# OSD19001_BREAKOUTS.net
KiCad netlist of a schematic drawn in Altium Designer
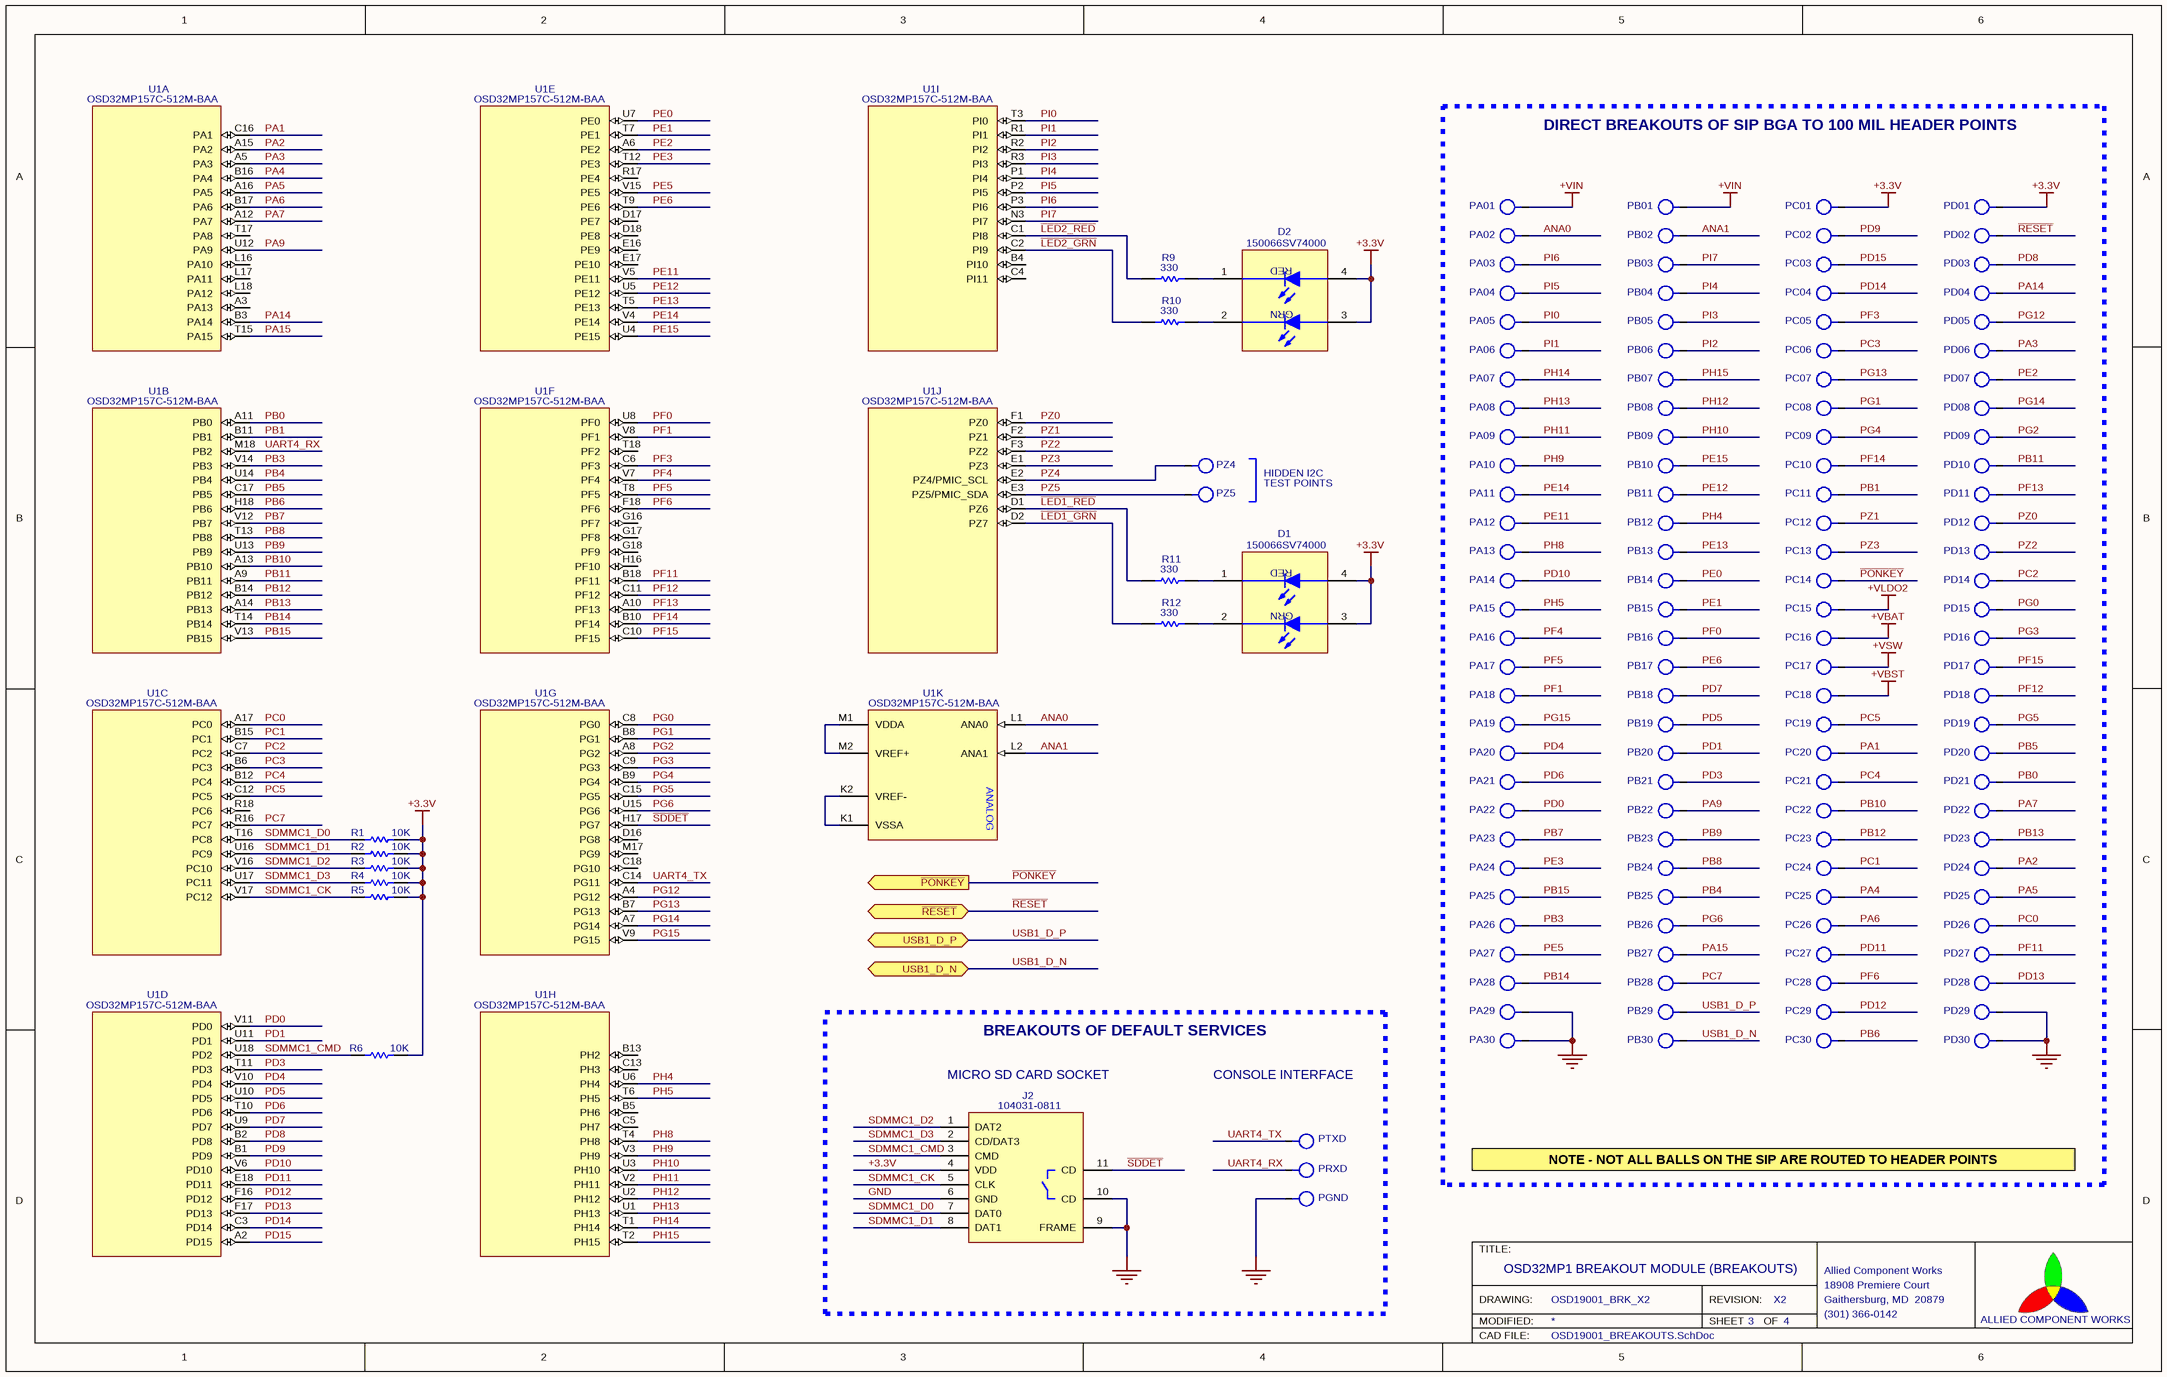
[diagram p0: OSD19001_BREAKOUTS.SchDoc]

(export (version "E")
  (design (tool "Eeschema 10.0.6"))
  (components
    (comp (ref "D1")
      (value "150066SV74000")
      (footprint "WURTH_DUAL_0606")
      (description "LED, Dual, 4-Wire, SMT")
      (libsource (lib "ACWSemiconductors") (part "LED_DUAL_0606_WURTH"))
    )
    (comp (ref "D2")
      (value "150066SV74000")
      (footprint "WURTH_DUAL_0606")
      (description "LED, Dual, 4-Wire, SMT")
      (libsource (lib "ACWSemiconductors") (part "LED_DUAL_0606_WURTH"))
    )
    (comp (ref "J2")
      (value "104031-0811")
      (footprint "MOLEX_104031-0811")
      (description "Micro SD Connector, With CD Switch")
      (libsource (lib "ACWConnectors") (part "SD_CARD_SW"))
    )
    (comp (ref "PA01")
      (value "TP")
      (footprint "LP_TESTPOINT_TH")
      (libsource (lib "ACWPrimitives") (part "TEST_POINT"))
    )
    (comp (ref "PA02")
      (value "TP")
      (footprint "LP_TESTPOINT_TH")
      (libsource (lib "ACWPrimitives") (part "TEST_POINT"))
    )
    (comp (ref "PA03")
      (value "TP")
      (footprint "LP_TESTPOINT_TH")
      (libsource (lib "ACWPrimitives") (part "TEST_POINT"))
    )
    (comp (ref "PA04")
      (value "TP")
      (footprint "LP_TESTPOINT_TH")
      (libsource (lib "ACWPrimitives") (part "TEST_POINT"))
    )
    (comp (ref "PA05")
      (value "TP")
      (footprint "LP_TESTPOINT_TH")
      (libsource (lib "ACWPrimitives") (part "TEST_POINT"))
    )
    (comp (ref "PA06")
      (value "TP")
      (footprint "LP_TESTPOINT_TH")
      (libsource (lib "ACWPrimitives") (part "TEST_POINT"))
    )
    (comp (ref "PA07")
      (value "TP")
      (footprint "LP_TESTPOINT_TH")
      (libsource (lib "ACWPrimitives") (part "TEST_POINT"))
    )
    (comp (ref "PA08")
      (value "TP")
      (footprint "LP_TESTPOINT_TH")
      (libsource (lib "ACWPrimitives") (part "TEST_POINT"))
    )
    (comp (ref "PA09")
      (value "TP")
      (footprint "LP_TESTPOINT_TH")
      (libsource (lib "ACWPrimitives") (part "TEST_POINT"))
    )
    (comp (ref "PA10")
      (value "TP")
      (footprint "LP_TESTPOINT_TH")
      (libsource (lib "ACWPrimitives") (part "TEST_POINT"))
    )
    (comp (ref "PA11")
      (value "TP")
      (footprint "LP_TESTPOINT_TH")
      (libsource (lib "ACWPrimitives") (part "TEST_POINT"))
    )
    (comp (ref "PA12")
      (value "TP")
      (footprint "LP_TESTPOINT_TH")
      (libsource (lib "ACWPrimitives") (part "TEST_POINT"))
    )
    (comp (ref "PA13")
      (value "TP")
      (footprint "LP_TESTPOINT_TH")
      (libsource (lib "ACWPrimitives") (part "TEST_POINT"))
    )
    (comp (ref "PA14")
      (value "TP")
      (footprint "LP_TESTPOINT_TH")
      (libsource (lib "ACWPrimitives") (part "TEST_POINT"))
    )
    (comp (ref "PA15")
      (value "TP")
      (footprint "LP_TESTPOINT_TH")
      (libsource (lib "ACWPrimitives") (part "TEST_POINT"))
    )
    (comp (ref "PA16")
      (value "TP")
      (footprint "LP_TESTPOINT_TH")
      (libsource (lib "ACWPrimitives") (part "TEST_POINT"))
    )
    (comp (ref "PA17")
      (value "TP")
      (footprint "LP_TESTPOINT_TH")
      (libsource (lib "ACWPrimitives") (part "TEST_POINT"))
    )
    (comp (ref "PA18")
      (value "TP")
      (footprint "LP_TESTPOINT_TH")
      (libsource (lib "ACWPrimitives") (part "TEST_POINT"))
    )
    (comp (ref "PA19")
      (value "TP")
      (footprint "LP_TESTPOINT_TH")
      (libsource (lib "ACWPrimitives") (part "TEST_POINT"))
    )
    (comp (ref "PA20")
      (value "TP")
      (footprint "LP_TESTPOINT_TH")
      (libsource (lib "ACWPrimitives") (part "TEST_POINT"))
    )
    (comp (ref "PA21")
      (value "TP")
      (footprint "LP_TESTPOINT_TH")
      (libsource (lib "ACWPrimitives") (part "TEST_POINT"))
    )
    (comp (ref "PA22")
      (value "TP")
      (footprint "LP_TESTPOINT_TH")
      (libsource (lib "ACWPrimitives") (part "TEST_POINT"))
    )
    (comp (ref "PA23")
      (value "TP")
      (footprint "LP_TESTPOINT_TH")
      (libsource (lib "ACWPrimitives") (part "TEST_POINT"))
    )
    (comp (ref "PA24")
      (value "TP")
      (footprint "LP_TESTPOINT_TH")
      (libsource (lib "ACWPrimitives") (part "TEST_POINT"))
    )
    (comp (ref "PA25")
      (value "TP")
      (footprint "LP_TESTPOINT_TH")
      (libsource (lib "ACWPrimitives") (part "TEST_POINT"))
    )
    (comp (ref "PA26")
      (value "TP")
      (footprint "LP_TESTPOINT_TH")
      (libsource (lib "ACWPrimitives") (part "TEST_POINT"))
    )
    (comp (ref "PA27")
      (value "TP")
      (footprint "LP_TESTPOINT_TH")
      (libsource (lib "ACWPrimitives") (part "TEST_POINT"))
    )
    (comp (ref "PA28")
      (value "TP")
      (footprint "LP_TESTPOINT_TH")
      (libsource (lib "ACWPrimitives") (part "TEST_POINT"))
    )
    (comp (ref "PA29")
      (value "TP")
      (footprint "LP_TESTPOINT_TH")
      (libsource (lib "ACWPrimitives") (part "TEST_POINT"))
    )
    (comp (ref "PA30")
      (value "TP")
      (footprint "LP_TESTPOINT_TH")
      (libsource (lib "ACWPrimitives") (part "TEST_POINT"))
    )
    (comp (ref "PB01")
      (value "TP")
      (footprint "LP_TESTPOINT_TH")
      (libsource (lib "ACWPrimitives") (part "TEST_POINT"))
    )
    (comp (ref "PB02")
      (value "TP")
      (footprint "LP_TESTPOINT_TH")
      (libsource (lib "ACWPrimitives") (part "TEST_POINT"))
    )
    (comp (ref "PB03")
      (value "TP")
      (footprint "LP_TESTPOINT_TH")
      (libsource (lib "ACWPrimitives") (part "TEST_POINT"))
    )
    (comp (ref "PB04")
      (value "TP")
      (footprint "LP_TESTPOINT_TH")
      (libsource (lib "ACWPrimitives") (part "TEST_POINT"))
    )
    (comp (ref "PB05")
      (value "TP")
      (footprint "LP_TESTPOINT_TH")
      (libsource (lib "ACWPrimitives") (part "TEST_POINT"))
    )
    (comp (ref "PB06")
      (value "TP")
      (footprint "LP_TESTPOINT_TH")
      (libsource (lib "ACWPrimitives") (part "TEST_POINT"))
    )
    (comp (ref "PB07")
      (value "TP")
      (footprint "LP_TESTPOINT_TH")
      (libsource (lib "ACWPrimitives") (part "TEST_POINT"))
    )
    (comp (ref "PB08")
      (value "TP")
      (footprint "LP_TESTPOINT_TH")
      (libsource (lib "ACWPrimitives") (part "TEST_POINT"))
    )
    (comp (ref "PB09")
      (value "TP")
      (footprint "LP_TESTPOINT_TH")
      (libsource (lib "ACWPrimitives") (part "TEST_POINT"))
    )
    (comp (ref "PB10")
      (value "TP")
      (footprint "LP_TESTPOINT_TH")
      (libsource (lib "ACWPrimitives") (part "TEST_POINT"))
    )
    (comp (ref "PB11")
      (value "TP")
      (footprint "LP_TESTPOINT_TH")
      (libsource (lib "ACWPrimitives") (part "TEST_POINT"))
    )
    (comp (ref "PB12")
      (value "TP")
      (footprint "LP_TESTPOINT_TH")
      (libsource (lib "ACWPrimitives") (part "TEST_POINT"))
    )
    (comp (ref "PB13")
      (value "TP")
      (footprint "LP_TESTPOINT_TH")
      (libsource (lib "ACWPrimitives") (part "TEST_POINT"))
    )
    (comp (ref "PB14")
      (value "TP")
      (footprint "LP_TESTPOINT_TH")
      (libsource (lib "ACWPrimitives") (part "TEST_POINT"))
    )
    (comp (ref "PB15")
      (value "TP")
      (footprint "LP_TESTPOINT_TH")
      (libsource (lib "ACWPrimitives") (part "TEST_POINT"))
    )
    (comp (ref "PB16")
      (value "TP")
      (footprint "LP_TESTPOINT_TH")
      (libsource (lib "ACWPrimitives") (part "TEST_POINT"))
    )
    (comp (ref "PB17")
      (value "TP")
      (footprint "LP_TESTPOINT_TH")
      (libsource (lib "ACWPrimitives") (part "TEST_POINT"))
    )
    (comp (ref "PB18")
      (value "TP")
      (footprint "LP_TESTPOINT_TH")
      (libsource (lib "ACWPrimitives") (part "TEST_POINT"))
    )
    (comp (ref "PB19")
      (value "TP")
      (footprint "LP_TESTPOINT_TH")
      (libsource (lib "ACWPrimitives") (part "TEST_POINT"))
    )
    (comp (ref "PB20")
      (value "TP")
      (footprint "LP_TESTPOINT_TH")
      (libsource (lib "ACWPrimitives") (part "TEST_POINT"))
    )
    (comp (ref "PB21")
      (value "TP")
      (footprint "LP_TESTPOINT_TH")
      (libsource (lib "ACWPrimitives") (part "TEST_POINT"))
    )
    (comp (ref "PB22")
      (value "TP")
      (footprint "LP_TESTPOINT_TH")
      (libsource (lib "ACWPrimitives") (part "TEST_POINT"))
    )
    (comp (ref "PB23")
      (value "TP")
      (footprint "LP_TESTPOINT_TH")
      (libsource (lib "ACWPrimitives") (part "TEST_POINT"))
    )
    (comp (ref "PB24")
      (value "TP")
      (footprint "LP_TESTPOINT_TH")
      (libsource (lib "ACWPrimitives") (part "TEST_POINT"))
    )
    (comp (ref "PB25")
      (value "TP")
      (footprint "LP_TESTPOINT_TH")
      (libsource (lib "ACWPrimitives") (part "TEST_POINT"))
    )
    (comp (ref "PB26")
      (value "TP")
      (footprint "LP_TESTPOINT_TH")
      (libsource (lib "ACWPrimitives") (part "TEST_POINT"))
    )
    (comp (ref "PB27")
      (value "TP")
      (footprint "LP_TESTPOINT_TH")
      (libsource (lib "ACWPrimitives") (part "TEST_POINT"))
    )
    (comp (ref "PB28")
      (value "TP")
      (footprint "LP_TESTPOINT_TH")
      (libsource (lib "ACWPrimitives") (part "TEST_POINT"))
    )
    (comp (ref "PB29")
      (value "TP")
      (footprint "LP_TESTPOINT_TH")
      (libsource (lib "ACWPrimitives") (part "TEST_POINT"))
    )
    (comp (ref "PB30")
      (value "TP")
      (footprint "LP_TESTPOINT_TH")
      (libsource (lib "ACWPrimitives") (part "TEST_POINT"))
    )
    (comp (ref "PC01")
      (value "TP")
      (footprint "LP_TESTPOINT_TH")
      (libsource (lib "ACWPrimitives") (part "TEST_POINT"))
    )
    (comp (ref "PC02")
      (value "TP")
      (footprint "LP_TESTPOINT_TH")
      (libsource (lib "ACWPrimitives") (part "TEST_POINT"))
    )
    (comp (ref "PC03")
      (value "TP")
      (footprint "LP_TESTPOINT_TH")
      (libsource (lib "ACWPrimitives") (part "TEST_POINT"))
    )
    (comp (ref "PC04")
      (value "TP")
      (footprint "LP_TESTPOINT_TH")
      (libsource (lib "ACWPrimitives") (part "TEST_POINT"))
    )
    (comp (ref "PC05")
      (value "TP")
      (footprint "LP_TESTPOINT_TH")
      (libsource (lib "ACWPrimitives") (part "TEST_POINT"))
    )
    (comp (ref "PC06")
      (value "TP")
      (footprint "LP_TESTPOINT_TH")
      (libsource (lib "ACWPrimitives") (part "TEST_POINT"))
    )
    (comp (ref "PC07")
      (value "TP")
      (footprint "LP_TESTPOINT_TH")
      (libsource (lib "ACWPrimitives") (part "TEST_POINT"))
    )
    (comp (ref "PC08")
      (value "TP")
      (footprint "LP_TESTPOINT_TH")
      (libsource (lib "ACWPrimitives") (part "TEST_POINT"))
    )
    (comp (ref "PC09")
      (value "TP")
      (footprint "LP_TESTPOINT_TH")
      (libsource (lib "ACWPrimitives") (part "TEST_POINT"))
    )
    (comp (ref "PC10")
      (value "TP")
      (footprint "LP_TESTPOINT_TH")
      (libsource (lib "ACWPrimitives") (part "TEST_POINT"))
    )
    (comp (ref "PC11")
      (value "TP")
      (footprint "LP_TESTPOINT_TH")
      (libsource (lib "ACWPrimitives") (part "TEST_POINT"))
    )
    (comp (ref "PC12")
      (value "TP")
      (footprint "LP_TESTPOINT_TH")
      (libsource (lib "ACWPrimitives") (part "TEST_POINT"))
    )
    (comp (ref "PC13")
      (value "TP")
      (footprint "LP_TESTPOINT_TH")
      (libsource (lib "ACWPrimitives") (part "TEST_POINT"))
    )
    (comp (ref "PC14")
      (value "TP")
      (footprint "LP_TESTPOINT_TH")
      (libsource (lib "ACWPrimitives") (part "TEST_POINT"))
    )
    (comp (ref "PC15")
      (value "TP")
      (footprint "LP_TESTPOINT_TH")
      (libsource (lib "ACWPrimitives") (part "TEST_POINT"))
    )
    (comp (ref "PC16")
      (value "TP")
      (footprint "LP_TESTPOINT_TH")
      (libsource (lib "ACWPrimitives") (part "TEST_POINT"))
    )
    (comp (ref "PC17")
      (value "TP")
      (footprint "LP_TESTPOINT_TH")
      (libsource (lib "ACWPrimitives") (part "TEST_POINT"))
    )
    (comp (ref "PC18")
      (value "TP")
      (footprint "LP_TESTPOINT_TH")
      (libsource (lib "ACWPrimitives") (part "TEST_POINT"))
    )
    (comp (ref "PC19")
      (value "TP")
      (footprint "LP_TESTPOINT_TH")
      (libsource (lib "ACWPrimitives") (part "TEST_POINT"))
    )
    (comp (ref "PC20")
      (value "TP")
      (footprint "LP_TESTPOINT_TH")
      (libsource (lib "ACWPrimitives") (part "TEST_POINT"))
    )
    (comp (ref "PC21")
      (value "TP")
      (footprint "LP_TESTPOINT_TH")
      (libsource (lib "ACWPrimitives") (part "TEST_POINT"))
    )
    (comp (ref "PC22")
      (value "TP")
      (footprint "LP_TESTPOINT_TH")
      (libsource (lib "ACWPrimitives") (part "TEST_POINT"))
    )
    (comp (ref "PC23")
      (value "TP")
      (footprint "LP_TESTPOINT_TH")
      (libsource (lib "ACWPrimitives") (part "TEST_POINT"))
    )
    (comp (ref "PC24")
      (value "TP")
      (footprint "LP_TESTPOINT_TH")
      (libsource (lib "ACWPrimitives") (part "TEST_POINT"))
    )
    (comp (ref "PC25")
      (value "TP")
      (footprint "LP_TESTPOINT_TH")
      (libsource (lib "ACWPrimitives") (part "TEST_POINT"))
    )
    (comp (ref "PC26")
      (value "TP")
      (footprint "LP_TESTPOINT_TH")
      (libsource (lib "ACWPrimitives") (part "TEST_POINT"))
    )
    (comp (ref "PC27")
      (value "TP")
      (footprint "LP_TESTPOINT_TH")
      (libsource (lib "ACWPrimitives") (part "TEST_POINT"))
    )
    (comp (ref "PC28")
      (value "TP")
      (footprint "LP_TESTPOINT_TH")
      (libsource (lib "ACWPrimitives") (part "TEST_POINT"))
    )
    (comp (ref "PC29")
      (value "TP")
      (footprint "LP_TESTPOINT_TH")
      (libsource (lib "ACWPrimitives") (part "TEST_POINT"))
    )
    (comp (ref "PC30")
      (value "TP")
      (footprint "LP_TESTPOINT_TH")
      (libsource (lib "ACWPrimitives") (part "TEST_POINT"))
    )
    (comp (ref "PD01")
      (value "TP")
      (footprint "LP_TESTPOINT_TH")
      (libsource (lib "ACWPrimitives") (part "TEST_POINT"))
    )
    (comp (ref "PD02")
      (value "TP")
      (footprint "LP_TESTPOINT_TH")
      (libsource (lib "ACWPrimitives") (part "TEST_POINT"))
    )
    (comp (ref "PD03")
      (value "TP")
      (footprint "LP_TESTPOINT_TH")
      (libsource (lib "ACWPrimitives") (part "TEST_POINT"))
    )
    (comp (ref "PD04")
      (value "TP")
      (footprint "LP_TESTPOINT_TH")
      (libsource (lib "ACWPrimitives") (part "TEST_POINT"))
    )
    (comp (ref "PD05")
      (value "TP")
      (footprint "LP_TESTPOINT_TH")
      (libsource (lib "ACWPrimitives") (part "TEST_POINT"))
    )
    (comp (ref "PD06")
      (value "TP")
      (footprint "LP_TESTPOINT_TH")
      (libsource (lib "ACWPrimitives") (part "TEST_POINT"))
    )
    (comp (ref "PD07")
      (value "TP")
      (footprint "LP_TESTPOINT_TH")
      (libsource (lib "ACWPrimitives") (part "TEST_POINT"))
    )
    (comp (ref "PD08")
      (value "TP")
      (footprint "LP_TESTPOINT_TH")
      (libsource (lib "ACWPrimitives") (part "TEST_POINT"))
    )
    (comp (ref "PD09")
      (value "TP")
      (footprint "LP_TESTPOINT_TH")
      (libsource (lib "ACWPrimitives") (part "TEST_POINT"))
    )
    (comp (ref "PD10")
      (value "TP")
      (footprint "LP_TESTPOINT_TH")
      (libsource (lib "ACWPrimitives") (part "TEST_POINT"))
    )
    (comp (ref "PD11")
      (value "TP")
      (footprint "LP_TESTPOINT_TH")
      (libsource (lib "ACWPrimitives") (part "TEST_POINT"))
    )
    (comp (ref "PD12")
      (value "TP")
      (footprint "LP_TESTPOINT_TH")
      (libsource (lib "ACWPrimitives") (part "TEST_POINT"))
    )
    (comp (ref "PD13")
      (value "TP")
      (footprint "LP_TESTPOINT_TH")
      (libsource (lib "ACWPrimitives") (part "TEST_POINT"))
    )
    (comp (ref "PD14")
      (value "TP")
      (footprint "LP_TESTPOINT_TH")
      (libsource (lib "ACWPrimitives") (part "TEST_POINT"))
    )
    (comp (ref "PD15")
      (value "TP")
      (footprint "LP_TESTPOINT_TH")
      (libsource (lib "ACWPrimitives") (part "TEST_POINT"))
    )
    (comp (ref "PD16")
      (value "TP")
      (footprint "LP_TESTPOINT_TH")
      (libsource (lib "ACWPrimitives") (part "TEST_POINT"))
    )
    (comp (ref "PD17")
      (value "TP")
      (footprint "LP_TESTPOINT_TH")
      (libsource (lib "ACWPrimitives") (part "TEST_POINT"))
    )
    (comp (ref "PD18")
      (value "TP")
      (footprint "LP_TESTPOINT_TH")
      (libsource (lib "ACWPrimitives") (part "TEST_POINT"))
    )
    (comp (ref "PD19")
      (value "TP")
      (footprint "LP_TESTPOINT_TH")
      (libsource (lib "ACWPrimitives") (part "TEST_POINT"))
    )
    (comp (ref "PD20")
      (value "TP")
      (footprint "LP_TESTPOINT_TH")
      (libsource (lib "ACWPrimitives") (part "TEST_POINT"))
    )
    (comp (ref "PD21")
      (value "TP")
      (footprint "LP_TESTPOINT_TH")
      (libsource (lib "ACWPrimitives") (part "TEST_POINT"))
    )
    (comp (ref "PD22")
      (value "TP")
      (footprint "LP_TESTPOINT_TH")
      (libsource (lib "ACWPrimitives") (part "TEST_POINT"))
    )
    (comp (ref "PD23")
      (value "TP")
      (footprint "LP_TESTPOINT_TH")
      (libsource (lib "ACWPrimitives") (part "TEST_POINT"))
    )
    (comp (ref "PD24")
      (value "TP")
      (footprint "LP_TESTPOINT_TH")
      (libsource (lib "ACWPrimitives") (part "TEST_POINT"))
    )
    (comp (ref "PD25")
      (value "TP")
      (footprint "LP_TESTPOINT_TH")
      (libsource (lib "ACWPrimitives") (part "TEST_POINT"))
    )
    (comp (ref "PD26")
      (value "TP")
      (footprint "LP_TESTPOINT_TH")
      (libsource (lib "ACWPrimitives") (part "TEST_POINT"))
    )
    (comp (ref "PD27")
      (value "TP")
      (footprint "LP_TESTPOINT_TH")
      (libsource (lib "ACWPrimitives") (part "TEST_POINT"))
    )
    (comp (ref "PD28")
      (value "TP")
      (footprint "LP_TESTPOINT_TH")
      (libsource (lib "ACWPrimitives") (part "TEST_POINT"))
    )
    (comp (ref "PD29")
      (value "TP")
      (footprint "LP_TESTPOINT_TH")
      (libsource (lib "ACWPrimitives") (part "TEST_POINT"))
    )
    (comp (ref "PD30")
      (value "TP")
      (footprint "LP_TESTPOINT_TH")
      (libsource (lib "ACWPrimitives") (part "TEST_POINT"))
    )
    (comp (ref "PGND")
      (value "TP")
      (footprint "LP_TESTPOINT_TH")
      (libsource (lib "ACWPrimitives") (part "TEST_POINT"))
    )
    (comp (ref "PRXD")
      (value "TP")
      (footprint "LP_TESTPOINT_TH")
      (libsource (lib "ACWPrimitives") (part "TEST_POINT"))
    )
    (comp (ref "PTXD")
      (value "TP")
      (footprint "LP_TESTPOINT_TH")
      (libsource (lib "ACWPrimitives") (part "TEST_POINT"))
    )
    (comp (ref "PZ4")
      (value "TP")
      (footprint "LP_TESTPOINT_SMT")
      (libsource (lib "ACWPrimitives") (part "TEST_POINT"))
    )
    (comp (ref "PZ5")
      (value "TP")
      (footprint "LP_TESTPOINT_SMT")
      (libsource (lib "ACWPrimitives") (part "TEST_POINT"))
    )
    (comp (ref "R1")
      (value "10K")
      (footprint "LP_0402_LOW")
      (fields (field (name "TOLERANCE") "5%") (field (name "POWER") "0.1W") (field (name "VOLTAGE") "50V"))
      (libsource (lib "ACWPrimitives") (part "RESISTOR"))
    )
    (comp (ref "R2")
      (value "10K")
      (footprint "LP_0402_LOW")
      (fields (field (name "TOLERANCE") "5%") (field (name "POWER") "0.1W") (field (name "VOLTAGE") "50V"))
      (libsource (lib "ACWPrimitives") (part "RESISTOR"))
    )
    (comp (ref "R3")
      (value "10K")
      (footprint "LP_0402_LOW")
      (fields (field (name "TOLERANCE") "5%") (field (name "POWER") "0.1W") (field (name "VOLTAGE") "50V"))
      (libsource (lib "ACWPrimitives") (part "RESISTOR"))
    )
    (comp (ref "R4")
      (value "10K")
      (footprint "LP_0402_LOW")
      (fields (field (name "TOLERANCE") "5%") (field (name "POWER") "0.1W") (field (name "VOLTAGE") "50V"))
      (libsource (lib "ACWPrimitives") (part "RESISTOR"))
    )
    (comp (ref "R5")
      (value "10K")
      (footprint "LP_0402_LOW")
      (fields (field (name "TOLERANCE") "5%") (field (name "POWER") "0.1W") (field (name "VOLTAGE") "50V"))
      (libsource (lib "ACWPrimitives") (part "RESISTOR"))
    )
    (comp (ref "R6")
      (value "10K")
      (footprint "LP_0402_LOW")
      (fields (field (name "TOLERANCE") "5%") (field (name "POWER") "0.1W") (field (name "VOLTAGE") "50V"))
      (libsource (lib "ACWPrimitives") (part "RESISTOR"))
    )
    (comp (ref "R9")
      (value "330")
      (footprint "LP_0402_LOW")
      (fields (field (name "TOLERANCE") "5%") (field (name "POWER") "0.1W") (field (name "VOLTAGE") "50V"))
      (libsource (lib "ACWPrimitives") (part "RESISTOR"))
    )
    (comp (ref "R10")
      (value "330")
      (footprint "LP_0402_LOW")
      (fields (field (name "TOLERANCE") "5%") (field (name "POWER") "0.1W") (field (name "VOLTAGE") "50V"))
      (libsource (lib "ACWPrimitives") (part "RESISTOR"))
    )
    (comp (ref "R11")
      (value "330")
      (footprint "LP_0402_LOW")
      (fields (field (name "TOLERANCE") "5%") (field (name "POWER") "0.1W") (field (name "VOLTAGE") "50V"))
      (libsource (lib "ACWPrimitives") (part "RESISTOR"))
    )
    (comp (ref "R12")
      (value "330")
      (footprint "LP_0402_LOW")
      (fields (field (name "TOLERANCE") "5%") (field (name "POWER") "0.1W") (field (name "VOLTAGE") "50V"))
      (libsource (lib "ACWPrimitives") (part "RESISTOR"))
    )
    (comp (ref "U1")
      (value "OSD32MP157C-512M-BAA")
      (footprint "BGA_OCTAVO_SIP_OSD32MP157C")
      (description "Octavo ST Processor SIP")
      (fields (field (name "MANUFACTURER") "Octavo Systems"))
      (libsource (lib "ACWModules") (part "OSD32MP157C"))
    )
  )
  (nets
    (net (code "1") (name "+3.3V") (class "Default")
      (node (ref "D1") (pin "3") (pinfunction "A_3") (pintype "passive"))
      (node (ref "D1") (pin "4") (pinfunction "A_4") (pintype "passive"))
      (node (ref "D2") (pin "3") (pinfunction "A_3") (pintype "passive"))
      (node (ref "D2") (pin "4") (pinfunction "A_4") (pintype "passive"))
      (node (ref "J2") (pin "4") (pinfunction "VDD_4") (pintype "passive"))
      (node (ref "PC01") (pin "1") (pinfunction "1_1") (pintype "passive"))
      (node (ref "PD01") (pin "1") (pinfunction "1_1") (pintype "passive"))
      (node (ref "R1") (pin "2") (pinfunction "2_2") (pintype "passive"))
      (node (ref "R2") (pin "2") (pinfunction "2_2") (pintype "passive"))
      (node (ref "R3") (pin "2") (pinfunction "2_2") (pintype "passive"))
      (node (ref "R4") (pin "2") (pinfunction "2_2") (pintype "passive"))
      (node (ref "R5") (pin "2") (pinfunction "2_2") (pintype "passive"))
      (node (ref "R6") (pin "2") (pinfunction "2_2") (pintype "passive"))
    )
    (net (code "2") (name "+VBAT") (class "Default")
      (node (ref "PC16") (pin "1") (pinfunction "1_1") (pintype "passive"))
    )
    (net (code "3") (name "+VBST") (class "Default")
      (node (ref "PC18") (pin "1") (pinfunction "1_1") (pintype "passive"))
    )
    (net (code "4") (name "+VIN") (class "Default")
      (node (ref "PA01") (pin "1") (pinfunction "1_1") (pintype "passive"))
      (node (ref "PB01") (pin "1") (pinfunction "1_1") (pintype "passive"))
    )
    (net (code "5") (name "+VLDO2") (class "Default")
      (node (ref "PC15") (pin "1") (pinfunction "1_1") (pintype "passive"))
    )
    (net (code "6") (name "+VSW") (class "Default")
      (node (ref "PC17") (pin "1") (pinfunction "1_1") (pintype "passive"))
    )
    (net (code "7") (name "/ANA0") (class "Default")
      (node (ref "PA02") (pin "1") (pinfunction "1_1") (pintype "passive"))
      (node (ref "U1") (pin "L1") (pinfunction "ANA0_L1") (pintype "input"))
    )
    (net (code "8") (name "/ANA1") (class "Default")
      (node (ref "PB02") (pin "1") (pinfunction "1_1") (pintype "passive"))
      (node (ref "U1") (pin "L2") (pinfunction "ANA1_L2") (pintype "input"))
    )
    (net (code "9") (name "/LED1_GRN") (class "Default")
      (node (ref "R12") (pin "1") (pinfunction "1_1") (pintype "passive"))
      (node (ref "U1") (pin "D2") (pinfunction "PZ7_D2") (pintype "bidirectional"))
    )
    (net (code "10") (name "/LED1_RED") (class "Default")
      (node (ref "R11") (pin "1") (pinfunction "1_1") (pintype "passive"))
      (node (ref "U1") (pin "D1") (pinfunction "PZ6_D1") (pintype "bidirectional"))
    )
    (net (code "11") (name "/LED2_GRN") (class "Default")
      (node (ref "R10") (pin "1") (pinfunction "1_1") (pintype "passive"))
      (node (ref "U1") (pin "C2") (pinfunction "PI9_C2") (pintype "bidirectional"))
    )
    (net (code "12") (name "/LED2_RED") (class "Default")
      (node (ref "R9") (pin "1") (pinfunction "1_1") (pintype "passive"))
      (node (ref "U1") (pin "C1") (pinfunction "PI8_C1") (pintype "bidirectional"))
    )
    (net (code "13") (name "/PA1") (class "Default")
      (node (ref "PC20") (pin "1") (pinfunction "1_1") (pintype "passive"))
      (node (ref "U1") (pin "C16") (pinfunction "PA1_C16") (pintype "bidirectional"))
    )
    (net (code "14") (name "/PA2") (class "Default")
      (node (ref "PD24") (pin "1") (pinfunction "1_1") (pintype "passive"))
      (node (ref "U1") (pin "A15") (pinfunction "PA2_A15") (pintype "bidirectional"))
    )
    (net (code "15") (name "/PA3") (class "Default")
      (node (ref "PD06") (pin "1") (pinfunction "1_1") (pintype "passive"))
      (node (ref "U1") (pin "A5") (pinfunction "PA3_A5") (pintype "bidirectional"))
    )
    (net (code "16") (name "/PA4") (class "Default")
      (node (ref "PC25") (pin "1") (pinfunction "1_1") (pintype "passive"))
      (node (ref "U1") (pin "B16") (pinfunction "PA4_B16") (pintype "bidirectional"))
    )
    (net (code "17") (name "/PA5") (class "Default")
      (node (ref "PD25") (pin "1") (pinfunction "1_1") (pintype "passive"))
      (node (ref "U1") (pin "A16") (pinfunction "PA5_A16") (pintype "bidirectional"))
    )
    (net (code "18") (name "/PA6") (class "Default")
      (node (ref "PC26") (pin "1") (pinfunction "1_1") (pintype "passive"))
      (node (ref "U1") (pin "B17") (pinfunction "PA6_B17") (pintype "bidirectional"))
    )
    (net (code "19") (name "/PA7") (class "Default")
      (node (ref "PD22") (pin "1") (pinfunction "1_1") (pintype "passive"))
      (node (ref "U1") (pin "A12") (pinfunction "PA7_A12") (pintype "bidirectional"))
    )
    (net (code "20") (name "/PA9") (class "Default")
      (node (ref "PB22") (pin "1") (pinfunction "1_1") (pintype "passive"))
      (node (ref "U1") (pin "U12") (pinfunction "PA9_U12") (pintype "bidirectional"))
    )
    (net (code "21") (name "/PA14") (class "Default")
      (node (ref "PD04") (pin "1") (pinfunction "1_1") (pintype "passive"))
      (node (ref "U1") (pin "B3") (pinfunction "PA14_B3") (pintype "bidirectional"))
    )
    (net (code "22") (name "/PA15") (class "Default")
      (node (ref "PB27") (pin "1") (pinfunction "1_1") (pintype "passive"))
      (node (ref "U1") (pin "T15") (pinfunction "PA15_T15") (pintype "bidirectional"))
    )
    (net (code "23") (name "/PB0") (class "Default")
      (node (ref "PD21") (pin "1") (pinfunction "1_1") (pintype "passive"))
      (node (ref "U1") (pin "A11") (pinfunction "PB0_A11") (pintype "bidirectional"))
    )
    (net (code "24") (name "/PB1") (class "Default")
      (node (ref "PC11") (pin "1") (pinfunction "1_1") (pintype "passive"))
      (node (ref "U1") (pin "B11") (pinfunction "PB1_B11") (pintype "bidirectional"))
    )
    (net (code "25") (name "/PB3") (class "Default")
      (node (ref "PA26") (pin "1") (pinfunction "1_1") (pintype "passive"))
      (node (ref "U1") (pin "V14") (pinfunction "PB3_V14") (pintype "bidirectional"))
    )
    (net (code "26") (name "/PB4") (class "Default")
      (node (ref "PB25") (pin "1") (pinfunction "1_1") (pintype "passive"))
      (node (ref "U1") (pin "U14") (pinfunction "PB4_U14") (pintype "bidirectional"))
    )
    (net (code "27") (name "/PB5") (class "Default")
      (node (ref "PD20") (pin "1") (pinfunction "1_1") (pintype "passive"))
      (node (ref "U1") (pin "C17") (pinfunction "PB5_C17") (pintype "bidirectional"))
    )
    (net (code "28") (name "/PB6") (class "Default")
      (node (ref "PC30") (pin "1") (pinfunction "1_1") (pintype "passive"))
      (node (ref "U1") (pin "H18") (pinfunction "PB6_H18") (pintype "bidirectional"))
    )
    (net (code "29") (name "/PB7") (class "Default")
      (node (ref "PA23") (pin "1") (pinfunction "1_1") (pintype "passive"))
      (node (ref "U1") (pin "V12") (pinfunction "PB7_V12") (pintype "bidirectional"))
    )
    (net (code "30") (name "/PB8") (class "Default")
      (node (ref "PB24") (pin "1") (pinfunction "1_1") (pintype "passive"))
      (node (ref "U1") (pin "T13") (pinfunction "PB8_T13") (pintype "bidirectional"))
    )
    (net (code "31") (name "/PB9") (class "Default")
      (node (ref "PB23") (pin "1") (pinfunction "1_1") (pintype "passive"))
      (node (ref "U1") (pin "U13") (pinfunction "PB9_U13") (pintype "bidirectional"))
    )
    (net (code "32") (name "/PB10") (class "Default")
      (node (ref "PC22") (pin "1") (pinfunction "1_1") (pintype "passive"))
      (node (ref "U1") (pin "A13") (pinfunction "PB10_A13") (pintype "bidirectional"))
    )
    (net (code "33") (name "/PB11") (class "Default")
      (node (ref "PD10") (pin "1") (pinfunction "1_1") (pintype "passive"))
      (node (ref "U1") (pin "A9") (pinfunction "PB11_A9") (pintype "bidirectional"))
    )
    (net (code "34") (name "/PB12") (class "Default")
      (node (ref "PC23") (pin "1") (pinfunction "1_1") (pintype "passive"))
      (node (ref "U1") (pin "B14") (pinfunction "PB12_B14") (pintype "bidirectional"))
    )
    (net (code "35") (name "/PB13") (class "Default")
      (node (ref "PD23") (pin "1") (pinfunction "1_1") (pintype "passive"))
      (node (ref "U1") (pin "A14") (pinfunction "PB13_A14") (pintype "bidirectional"))
    )
    (net (code "36") (name "/PB14") (class "Default")
      (node (ref "PA28") (pin "1") (pinfunction "1_1") (pintype "passive"))
      (node (ref "U1") (pin "T14") (pinfunction "PB14_T14") (pintype "bidirectional"))
    )
    (net (code "37") (name "/PB15") (class "Default")
      (node (ref "PA25") (pin "1") (pinfunction "1_1") (pintype "passive"))
      (node (ref "U1") (pin "V13") (pinfunction "PB15_V13") (pintype "bidirectional"))
    )
    (net (code "38") (name "/PC0") (class "Default")
      (node (ref "PD26") (pin "1") (pinfunction "1_1") (pintype "passive"))
      (node (ref "U1") (pin "A17") (pinfunction "PC0_A17") (pintype "bidirectional"))
    )
    (net (code "39") (name "/PC1") (class "Default")
      (node (ref "PC24") (pin "1") (pinfunction "1_1") (pintype "passive"))
      (node (ref "U1") (pin "B15") (pinfunction "PC1_B15") (pintype "bidirectional"))
    )
    (net (code "40") (name "/PC2") (class "Default")
      (node (ref "PD14") (pin "1") (pinfunction "1_1") (pintype "passive"))
      (node (ref "U1") (pin "C7") (pinfunction "PC2_C7") (pintype "bidirectional"))
    )
    (net (code "41") (name "/PC3") (class "Default")
      (node (ref "PC06") (pin "1") (pinfunction "1_1") (pintype "passive"))
      (node (ref "U1") (pin "B6") (pinfunction "PC3_B6") (pintype "bidirectional"))
    )
    (net (code "42") (name "/PC4") (class "Default")
      (node (ref "PC21") (pin "1") (pinfunction "1_1") (pintype "passive"))
      (node (ref "U1") (pin "B12") (pinfunction "PC4_B12") (pintype "bidirectional"))
    )
    (net (code "43") (name "/PC5") (class "Default")
      (node (ref "PC19") (pin "1") (pinfunction "1_1") (pintype "passive"))
      (node (ref "U1") (pin "C12") (pinfunction "PC5_C12") (pintype "bidirectional"))
    )
    (net (code "44") (name "/PC7") (class "Default")
      (node (ref "PB28") (pin "1") (pinfunction "1_1") (pintype "passive"))
      (node (ref "U1") (pin "R16") (pinfunction "PC7_R16") (pintype "bidirectional"))
    )
    (net (code "45") (name "/PD0") (class "Default")
      (node (ref "PA22") (pin "1") (pinfunction "1_1") (pintype "passive"))
      (node (ref "U1") (pin "V11") (pinfunction "PD0_V11") (pintype "bidirectional"))
    )
    (net (code "46") (name "/PD1") (class "Default")
      (node (ref "PB20") (pin "1") (pinfunction "1_1") (pintype "passive"))
      (node (ref "U1") (pin "U11") (pinfunction "PD1_U11") (pintype "bidirectional"))
    )
    (net (code "47") (name "/PD3") (class "Default")
      (node (ref "PB21") (pin "1") (pinfunction "1_1") (pintype "passive"))
      (node (ref "U1") (pin "T11") (pinfunction "PD3_T11") (pintype "bidirectional"))
    )
    (net (code "48") (name "/PD4") (class "Default")
      (node (ref "PA20") (pin "1") (pinfunction "1_1") (pintype "passive"))
      (node (ref "U1") (pin "V10") (pinfunction "PD4_V10") (pintype "bidirectional"))
    )
    (net (code "49") (name "/PD5") (class "Default")
      (node (ref "PB19") (pin "1") (pinfunction "1_1") (pintype "passive"))
      (node (ref "U1") (pin "U10") (pinfunction "PD5_U10") (pintype "bidirectional"))
    )
    (net (code "50") (name "/PD6") (class "Default")
      (node (ref "PA21") (pin "1") (pinfunction "1_1") (pintype "passive"))
      (node (ref "U1") (pin "T10") (pinfunction "PD6_T10") (pintype "bidirectional"))
    )
    (net (code "51") (name "/PD7") (class "Default")
      (node (ref "PB18") (pin "1") (pinfunction "1_1") (pintype "passive"))
      (node (ref "U1") (pin "U9") (pinfunction "PD7_U9") (pintype "bidirectional"))
    )
    (net (code "52") (name "/PD8") (class "Default")
      (node (ref "PD03") (pin "1") (pinfunction "1_1") (pintype "passive"))
      (node (ref "U1") (pin "B2") (pinfunction "PD8_B2") (pintype "bidirectional"))
    )
    (net (code "53") (name "/PD9") (class "Default")
      (node (ref "PC02") (pin "1") (pinfunction "1_1") (pintype "passive"))
      (node (ref "U1") (pin "B1") (pinfunction "PD9_B1") (pintype "bidirectional"))
    )
    (net (code "54") (name "/PD10") (class "Default")
      (node (ref "PA14") (pin "1") (pinfunction "1_1") (pintype "passive"))
      (node (ref "U1") (pin "V6") (pinfunction "PD10_V6") (pintype "bidirectional"))
    )
    (net (code "55") (name "/PD11") (class "Default")
      (node (ref "PC27") (pin "1") (pinfunction "1_1") (pintype "passive"))
      (node (ref "U1") (pin "E18") (pinfunction "PD11_E18") (pintype "bidirectional"))
    )
    (net (code "56") (name "/PD12") (class "Default")
      (node (ref "PC29") (pin "1") (pinfunction "1_1") (pintype "passive"))
      (node (ref "U1") (pin "F16") (pinfunction "PD12_F16") (pintype "bidirectional"))
    )
    (net (code "57") (name "/PD13") (class "Default")
      (node (ref "PD28") (pin "1") (pinfunction "1_1") (pintype "passive"))
      (node (ref "U1") (pin "F17") (pinfunction "PD13_F17") (pintype "bidirectional"))
    )
    (net (code "58") (name "/PD14") (class "Default")
      (node (ref "PC04") (pin "1") (pinfunction "1_1") (pintype "passive"))
      (node (ref "U1") (pin "C3") (pinfunction "PD14_C3") (pintype "bidirectional"))
    )
    (net (code "59") (name "/PD15") (class "Default")
      (node (ref "PC03") (pin "1") (pinfunction "1_1") (pintype "passive"))
      (node (ref "U1") (pin "A2") (pinfunction "PD15_A2") (pintype "bidirectional"))
    )
    (net (code "60") (name "/PE0") (class "Default")
      (node (ref "PB14") (pin "1") (pinfunction "1_1") (pintype "passive"))
      (node (ref "U1") (pin "U7") (pinfunction "PE0_U7") (pintype "bidirectional"))
    )
    (net (code "61") (name "/PE1") (class "Default")
      (node (ref "PB15") (pin "1") (pinfunction "1_1") (pintype "passive"))
      (node (ref "U1") (pin "T7") (pinfunction "PE1_T7") (pintype "bidirectional"))
    )
    (net (code "62") (name "/PE2") (class "Default")
      (node (ref "PD07") (pin "1") (pinfunction "1_1") (pintype "passive"))
      (node (ref "U1") (pin "A6") (pinfunction "PE2_A6") (pintype "bidirectional"))
    )
    (net (code "63") (name "/PE3") (class "Default")
      (node (ref "PA24") (pin "1") (pinfunction "1_1") (pintype "passive"))
      (node (ref "U1") (pin "T12") (pinfunction "PE3_T12") (pintype "bidirectional"))
    )
    (net (code "64") (name "/PE5") (class "Default")
      (node (ref "PA27") (pin "1") (pinfunction "1_1") (pintype "passive"))
      (node (ref "U1") (pin "V15") (pinfunction "PE5_V15") (pintype "bidirectional"))
    )
    (net (code "65") (name "/PE6") (class "Default")
      (node (ref "PB17") (pin "1") (pinfunction "1_1") (pintype "passive"))
      (node (ref "U1") (pin "T9") (pinfunction "PE6_T9") (pintype "bidirectional"))
    )
    (net (code "66") (name "/PE11") (class "Default")
      (node (ref "PA12") (pin "1") (pinfunction "1_1") (pintype "passive"))
      (node (ref "U1") (pin "V5") (pinfunction "PE11_V5") (pintype "bidirectional"))
    )
    (net (code "67") (name "/PE12") (class "Default")
      (node (ref "PB11") (pin "1") (pinfunction "1_1") (pintype "passive"))
      (node (ref "U1") (pin "U5") (pinfunction "PE12_U5") (pintype "bidirectional"))
    )
    (net (code "68") (name "/PE13") (class "Default")
      (node (ref "PB13") (pin "1") (pinfunction "1_1") (pintype "passive"))
      (node (ref "U1") (pin "T5") (pinfunction "PE13_T5") (pintype "bidirectional"))
    )
    (net (code "69") (name "/PE14") (class "Default")
      (node (ref "PA11") (pin "1") (pinfunction "1_1") (pintype "passive"))
      (node (ref "U1") (pin "V4") (pinfunction "PE14_V4") (pintype "bidirectional"))
    )
    (net (code "70") (name "/PE15") (class "Default")
      (node (ref "PB10") (pin "1") (pinfunction "1_1") (pintype "passive"))
      (node (ref "U1") (pin "U4") (pinfunction "PE15_U4") (pintype "bidirectional"))
    )
    (net (code "71") (name "/PF0") (class "Default")
      (node (ref "PB16") (pin "1") (pinfunction "1_1") (pintype "passive"))
      (node (ref "U1") (pin "U8") (pinfunction "PF0_U8") (pintype "bidirectional"))
    )
    (net (code "72") (name "/PF1") (class "Default")
      (node (ref "PA18") (pin "1") (pinfunction "1_1") (pintype "passive"))
      (node (ref "U1") (pin "V8") (pinfunction "PF1_V8") (pintype "bidirectional"))
    )
    (net (code "73") (name "/PF3") (class "Default")
      (node (ref "PC05") (pin "1") (pinfunction "1_1") (pintype "passive"))
      (node (ref "U1") (pin "C6") (pinfunction "PF3_C6") (pintype "bidirectional"))
    )
    (net (code "74") (name "/PF4") (class "Default")
      (node (ref "PA16") (pin "1") (pinfunction "1_1") (pintype "passive"))
      (node (ref "U1") (pin "V7") (pinfunction "PF4_V7") (pintype "bidirectional"))
    )
    (net (code "75") (name "/PF5") (class "Default")
      (node (ref "PA17") (pin "1") (pinfunction "1_1") (pintype "passive"))
      (node (ref "U1") (pin "T8") (pinfunction "PF5_T8") (pintype "bidirectional"))
    )
    (net (code "76") (name "/PF6") (class "Default")
      (node (ref "PC28") (pin "1") (pinfunction "1_1") (pintype "passive"))
      (node (ref "U1") (pin "F18") (pinfunction "PF6_F18") (pintype "bidirectional"))
    )
    (net (code "77") (name "/PF11") (class "Default")
      (node (ref "PD27") (pin "1") (pinfunction "1_1") (pintype "passive"))
      (node (ref "U1") (pin "B18") (pinfunction "PF11_B18") (pintype "bidirectional"))
    )
    (net (code "78") (name "/PF12") (class "Default")
      (node (ref "PD18") (pin "1") (pinfunction "1_1") (pintype "passive"))
      (node (ref "U1") (pin "C11") (pinfunction "PF12_C11") (pintype "bidirectional"))
    )
    (net (code "79") (name "/PF13") (class "Default")
      (node (ref "PD11") (pin "1") (pinfunction "1_1") (pintype "passive"))
      (node (ref "U1") (pin "A10") (pinfunction "PF13_A10") (pintype "bidirectional"))
    )
    (net (code "80") (name "/PF14") (class "Default")
      (node (ref "PC10") (pin "1") (pinfunction "1_1") (pintype "passive"))
      (node (ref "U1") (pin "B10") (pinfunction "PF14_B10") (pintype "bidirectional"))
    )
    (net (code "81") (name "/PF15") (class "Default")
      (node (ref "PD17") (pin "1") (pinfunction "1_1") (pintype "passive"))
      (node (ref "U1") (pin "C10") (pinfunction "PF15_C10") (pintype "bidirectional"))
    )
    (net (code "82") (name "/PG0") (class "Default")
      (node (ref "PD15") (pin "1") (pinfunction "1_1") (pintype "passive"))
      (node (ref "U1") (pin "C8") (pinfunction "PG0_C8") (pintype "bidirectional"))
    )
    (net (code "83") (name "/PG1") (class "Default")
      (node (ref "PC08") (pin "1") (pinfunction "1_1") (pintype "passive"))
      (node (ref "U1") (pin "B8") (pinfunction "PG1_B8") (pintype "bidirectional"))
    )
    (net (code "84") (name "/PG2") (class "Default")
      (node (ref "PD09") (pin "1") (pinfunction "1_1") (pintype "passive"))
      (node (ref "U1") (pin "A8") (pinfunction "PG2_A8") (pintype "bidirectional"))
    )
    (net (code "85") (name "/PG3") (class "Default")
      (node (ref "PD16") (pin "1") (pinfunction "1_1") (pintype "passive"))
      (node (ref "U1") (pin "C9") (pinfunction "PG3_C9") (pintype "bidirectional"))
    )
    (net (code "86") (name "/PG4") (class "Default")
      (node (ref "PC09") (pin "1") (pinfunction "1_1") (pintype "passive"))
      (node (ref "U1") (pin "B9") (pinfunction "PG4_B9") (pintype "bidirectional"))
    )
    (net (code "87") (name "/PG5") (class "Default")
      (node (ref "PD19") (pin "1") (pinfunction "1_1") (pintype "passive"))
      (node (ref "U1") (pin "C15") (pinfunction "PG5_C15") (pintype "bidirectional"))
    )
    (net (code "88") (name "/PG6") (class "Default")
      (node (ref "PB26") (pin "1") (pinfunction "1_1") (pintype "passive"))
      (node (ref "U1") (pin "U15") (pinfunction "PG6_U15") (pintype "bidirectional"))
    )
    (net (code "89") (name "/PG12") (class "Default")
      (node (ref "PD05") (pin "1") (pinfunction "1_1") (pintype "passive"))
      (node (ref "U1") (pin "A4") (pinfunction "PG12_A4") (pintype "bidirectional"))
    )
    (net (code "90") (name "/PG13") (class "Default")
      (node (ref "PC07") (pin "1") (pinfunction "1_1") (pintype "passive"))
      (node (ref "U1") (pin "B7") (pinfunction "PG13_B7") (pintype "bidirectional"))
    )
    (net (code "91") (name "/PG14") (class "Default")
      (node (ref "PD08") (pin "1") (pinfunction "1_1") (pintype "passive"))
      (node (ref "U1") (pin "A7") (pinfunction "PG14_A7") (pintype "bidirectional"))
    )
    (net (code "92") (name "/PG15") (class "Default")
      (node (ref "PA19") (pin "1") (pinfunction "1_1") (pintype "passive"))
      (node (ref "U1") (pin "V9") (pinfunction "PG15_V9") (pintype "bidirectional"))
    )
    (net (code "93") (name "/PH4") (class "Default")
      (node (ref "PB12") (pin "1") (pinfunction "1_1") (pintype "passive"))
      (node (ref "U1") (pin "U6") (pinfunction "PH4_U6") (pintype "bidirectional"))
    )
    (net (code "94") (name "/PH5") (class "Default")
      (node (ref "PA15") (pin "1") (pinfunction "1_1") (pintype "passive"))
      (node (ref "U1") (pin "T6") (pinfunction "PH5_T6") (pintype "bidirectional"))
    )
    (net (code "95") (name "/PH8") (class "Default")
      (node (ref "PA13") (pin "1") (pinfunction "1_1") (pintype "passive"))
      (node (ref "U1") (pin "T4") (pinfunction "PH8_T4") (pintype "bidirectional"))
    )
    (net (code "96") (name "/PH9") (class "Default")
      (node (ref "PA10") (pin "1") (pinfunction "1_1") (pintype "passive"))
      (node (ref "U1") (pin "V3") (pinfunction "PH9_V3") (pintype "bidirectional"))
    )
    (net (code "97") (name "/PH10") (class "Default")
      (node (ref "PB09") (pin "1") (pinfunction "1_1") (pintype "passive"))
      (node (ref "U1") (pin "U3") (pinfunction "PH10_U3") (pintype "bidirectional"))
    )
    (net (code "98") (name "/PH11") (class "Default")
      (node (ref "PA09") (pin "1") (pinfunction "1_1") (pintype "passive"))
      (node (ref "U1") (pin "V2") (pinfunction "PH11_V2") (pintype "bidirectional"))
    )
    (net (code "99") (name "/PH12") (class "Default")
      (node (ref "PB08") (pin "1") (pinfunction "1_1") (pintype "passive"))
      (node (ref "U1") (pin "U2") (pinfunction "PH12_U2") (pintype "bidirectional"))
    )
    (net (code "100") (name "/PH13") (class "Default")
      (node (ref "PA08") (pin "1") (pinfunction "1_1") (pintype "passive"))
      (node (ref "U1") (pin "U1") (pinfunction "PH13_U1") (pintype "bidirectional"))
    )
    (net (code "101") (name "/PH14") (class "Default")
      (node (ref "PA07") (pin "1") (pinfunction "1_1") (pintype "passive"))
      (node (ref "U1") (pin "T1") (pinfunction "PH14_T1") (pintype "bidirectional"))
    )
    (net (code "102") (name "/PH15") (class "Default")
      (node (ref "PB07") (pin "1") (pinfunction "1_1") (pintype "passive"))
      (node (ref "U1") (pin "T2") (pinfunction "PH15_T2") (pintype "bidirectional"))
    )
    (net (code "103") (name "/PI0") (class "Default")
      (node (ref "PA05") (pin "1") (pinfunction "1_1") (pintype "passive"))
      (node (ref "U1") (pin "T3") (pinfunction "PI0_T3") (pintype "bidirectional"))
    )
    (net (code "104") (name "/PI1") (class "Default")
      (node (ref "PA06") (pin "1") (pinfunction "1_1") (pintype "passive"))
      (node (ref "U1") (pin "R1") (pinfunction "PI1_R1") (pintype "bidirectional"))
    )
    (net (code "105") (name "/PI2") (class "Default")
      (node (ref "PB06") (pin "1") (pinfunction "1_1") (pintype "passive"))
      (node (ref "U1") (pin "R2") (pinfunction "PI2_R2") (pintype "bidirectional"))
    )
    (net (code "106") (name "/PI3") (class "Default")
      (node (ref "PB05") (pin "1") (pinfunction "1_1") (pintype "passive"))
      (node (ref "U1") (pin "R3") (pinfunction "PI3_R3") (pintype "bidirectional"))
    )
    (net (code "107") (name "/PI4") (class "Default")
      (node (ref "PB04") (pin "1") (pinfunction "1_1") (pintype "passive"))
      (node (ref "U1") (pin "P1") (pinfunction "PI4_P1") (pintype "bidirectional"))
    )
    (net (code "108") (name "/PI5") (class "Default")
      (node (ref "PA04") (pin "1") (pinfunction "1_1") (pintype "passive"))
      (node (ref "U1") (pin "P2") (pinfunction "PI5_P2") (pintype "bidirectional"))
    )
    (net (code "109") (name "/PI6") (class "Default")
      (node (ref "PA03") (pin "1") (pinfunction "1_1") (pintype "passive"))
      (node (ref "U1") (pin "P3") (pinfunction "PI6_P3") (pintype "bidirectional"))
    )
    (net (code "110") (name "/PI7") (class "Default")
      (node (ref "PB03") (pin "1") (pinfunction "1_1") (pintype "passive"))
      (node (ref "U1") (pin "N3") (pinfunction "PI7_N3") (pintype "bidirectional"))
    )
    (net (code "111") (name "/PONKEY") (class "Default")
      (node (ref "PC14") (pin "1") (pinfunction "1_1") (pintype "passive"))
    )
    (net (code "112") (name "/PZ0") (class "Default")
      (node (ref "PD12") (pin "1") (pinfunction "1_1") (pintype "passive"))
      (node (ref "U1") (pin "F1") (pinfunction "PZ0_F1") (pintype "bidirectional"))
    )
    (net (code "113") (name "/PZ1") (class "Default")
      (node (ref "PC12") (pin "1") (pinfunction "1_1") (pintype "passive"))
      (node (ref "U1") (pin "F2") (pinfunction "PZ1_F2") (pintype "bidirectional"))
    )
    (net (code "114") (name "/PZ2") (class "Default")
      (node (ref "PD13") (pin "1") (pinfunction "1_1") (pintype "passive"))
      (node (ref "U1") (pin "F3") (pinfunction "PZ2_F3") (pintype "bidirectional"))
    )
    (net (code "115") (name "/PZ3") (class "Default")
      (node (ref "PC13") (pin "1") (pinfunction "1_1") (pintype "passive"))
      (node (ref "U1") (pin "E1") (pinfunction "PZ3_E1") (pintype "bidirectional"))
    )
    (net (code "116") (name "/PZ4") (class "Default")
      (node (ref "PZ4") (pin "1") (pinfunction "1_1") (pintype "passive"))
      (node (ref "U1") (pin "E2") (pinfunction "PZ4/PMIC_SCL_E2") (pintype "bidirectional"))
    )
    (net (code "117") (name "/PZ5") (class "Default")
      (node (ref "PZ5") (pin "1") (pinfunction "1_1") (pintype "passive"))
      (node (ref "U1") (pin "E3") (pinfunction "PZ5/PMIC_SDA_E3") (pintype "bidirectional"))
    )
    (net (code "118") (name "/RESET") (class "Default")
      (node (ref "PD02") (pin "1") (pinfunction "1_1") (pintype "passive"))
    )
    (net (code "119") (name "/SDDET") (class "Default")
      (node (ref "J2") (pin "11") (pinfunction "CD_11") (pintype "passive"))
      (node (ref "U1") (pin "H17") (pinfunction "PG7_H17") (pintype "bidirectional"))
    )
    (net (code "120") (name "/SDMMC1_CK") (class "Default")
      (node (ref "J2") (pin "5") (pinfunction "CLK_5") (pintype "passive"))
      (node (ref "R5") (pin "1") (pinfunction "1_1") (pintype "passive"))
      (node (ref "U1") (pin "V17") (pinfunction "PC12_V17") (pintype "bidirectional"))
    )
    (net (code "121") (name "/SDMMC1_CMD") (class "Default")
      (node (ref "J2") (pin "3") (pinfunction "CMD_3") (pintype "passive"))
      (node (ref "R6") (pin "1") (pinfunction "1_1") (pintype "passive"))
      (node (ref "U1") (pin "U18") (pinfunction "PD2_U18") (pintype "bidirectional"))
    )
    (net (code "122") (name "/SDMMC1_D0") (class "Default")
      (node (ref "J2") (pin "7") (pinfunction "DAT0_7") (pintype "passive"))
      (node (ref "R1") (pin "1") (pinfunction "1_1") (pintype "passive"))
      (node (ref "U1") (pin "T16") (pinfunction "PC8_T16") (pintype "bidirectional"))
    )
    (net (code "123") (name "/SDMMC1_D1") (class "Default")
      (node (ref "J2") (pin "8") (pinfunction "DAT1_8") (pintype "passive"))
      (node (ref "R2") (pin "1") (pinfunction "1_1") (pintype "passive"))
      (node (ref "U1") (pin "U16") (pinfunction "PC9_U16") (pintype "bidirectional"))
    )
    (net (code "124") (name "/SDMMC1_D2") (class "Default")
      (node (ref "J2") (pin "1") (pinfunction "DAT2_1") (pintype "passive"))
      (node (ref "R3") (pin "1") (pinfunction "1_1") (pintype "passive"))
      (node (ref "U1") (pin "V16") (pinfunction "PC10_V16") (pintype "bidirectional"))
    )
    (net (code "125") (name "/SDMMC1_D3") (class "Default")
      (node (ref "J2") (pin "2") (pinfunction "CD/DAT3_2") (pintype "passive"))
      (node (ref "R4") (pin "1") (pinfunction "1_1") (pintype "passive"))
      (node (ref "U1") (pin "U17") (pinfunction "PC11_U17") (pintype "bidirectional"))
    )
    (net (code "126") (name "/UART4_RX") (class "Default")
      (node (ref "PRXD") (pin "1") (pinfunction "1_1") (pintype "passive"))
      (node (ref "U1") (pin "M18") (pinfunction "PB2_M18") (pintype "bidirectional"))
    )
    (net (code "127") (name "/UART4_TX") (class "Default")
      (node (ref "PTXD") (pin "1") (pinfunction "1_1") (pintype "passive"))
      (node (ref "U1") (pin "C14") (pinfunction "PG11_C14") (pintype "bidirectional"))
    )
    (net (code "128") (name "/USB1_D_N") (class "Default")
      (node (ref "PB30") (pin "1") (pinfunction "1_1") (pintype "passive"))
    )
    (net (code "129") (name "/USB1_D_P") (class "Default")
      (node (ref "PB29") (pin "1") (pinfunction "1_1") (pintype "passive"))
    )
    (net (code "130") (name "GND") (class "Default")
      (node (ref "J2") (pin "10") (pinfunction "CD_10") (pintype "passive"))
      (node (ref "J2") (pin "6") (pinfunction "GND_6") (pintype "passive"))
      (node (ref "J2") (pin "9") (pinfunction "FRAME_9") (pintype "passive"))
      (node (ref "PA29") (pin "1") (pinfunction "1_1") (pintype "passive"))
      (node (ref "PA30") (pin "1") (pinfunction "1_1") (pintype "passive"))
      (node (ref "PD29") (pin "1") (pinfunction "1_1") (pintype "passive"))
      (node (ref "PD30") (pin "1") (pinfunction "1_1") (pintype "passive"))
      (node (ref "PGND") (pin "1") (pinfunction "1_1") (pintype "passive"))
    )
    (net (code "131") (name "Net-(D1-K-Pad1)") (class "Default")
      (node (ref "D1") (pin "1") (pinfunction "K_1") (pintype "passive"))
      (node (ref "R11") (pin "2") (pinfunction "2_2") (pintype "passive"))
    )
    (net (code "132") (name "Net-(D1-K-Pad2)") (class "Default")
      (node (ref "D1") (pin "2") (pinfunction "K_2") (pintype "passive"))
      (node (ref "R12") (pin "2") (pinfunction "2_2") (pintype "passive"))
    )
    (net (code "133") (name "Net-(D2-K-Pad1)") (class "Default")
      (node (ref "D2") (pin "1") (pinfunction "K_1") (pintype "passive"))
      (node (ref "R9") (pin "2") (pinfunction "2_2") (pintype "passive"))
    )
    (net (code "134") (name "Net-(D2-K-Pad2)") (class "Default")
      (node (ref "D2") (pin "2") (pinfunction "K_2") (pintype "passive"))
      (node (ref "R10") (pin "2") (pinfunction "2_2") (pintype "passive"))
    )
    (net (code "135") (name "Net-(U1K-VDDA)") (class "Default")
      (node (ref "U1") (pin "M1") (pinfunction "VDDA_M1") (pintype "passive"))
      (node (ref "U1") (pin "M2") (pinfunction "VREF+_M2") (pintype "passive"))
    )
    (net (code "136") (name "Net-(U1K-VREF-)") (class "Default")
      (node (ref "U1") (pin "K1") (pinfunction "VSSA_K1") (pintype "passive"))
      (node (ref "U1") (pin "K2") (pinfunction "VREF-_K2") (pintype "passive"))
    )
    (net (code "137") (name "unconnected-(U1A-PA8-PadT17)") (class "Default")
      (node (ref "U1") (pin "T17") (pinfunction "PA8_T17") (pintype "bidirectional"))
    )
    (net (code "138") (name "unconnected-(U1A-PA10-PadL16)") (class "Default")
      (node (ref "U1") (pin "L16") (pinfunction "PA10_L16") (pintype "bidirectional"))
    )
    (net (code "139") (name "unconnected-(U1A-PA11-PadL17)") (class "Default")
      (node (ref "U1") (pin "L17") (pinfunction "PA11_L17") (pintype "bidirectional"))
    )
    (net (code "140") (name "unconnected-(U1A-PA12-PadL18)") (class "Default")
      (node (ref "U1") (pin "L18") (pinfunction "PA12_L18") (pintype "bidirectional"))
    )
    (net (code "141") (name "unconnected-(U1A-PA13-PadA3)") (class "Default")
      (node (ref "U1") (pin "A3") (pinfunction "PA13_A3") (pintype "bidirectional"))
    )
    (net (code "142") (name "unconnected-(U1C-PC6-PadR18)") (class "Default")
      (node (ref "U1") (pin "R18") (pinfunction "PC6_R18") (pintype "bidirectional"))
    )
    (net (code "143") (name "unconnected-(U1E-PE4-PadR17)") (class "Default")
      (node (ref "U1") (pin "R17") (pinfunction "PE4_R17") (pintype "bidirectional"))
    )
    (net (code "144") (name "unconnected-(U1E-PE7-PadD17)") (class "Default")
      (node (ref "U1") (pin "D17") (pinfunction "PE7_D17") (pintype "bidirectional"))
    )
    (net (code "145") (name "unconnected-(U1E-PE8-PadD18)") (class "Default")
      (node (ref "U1") (pin "D18") (pinfunction "PE8_D18") (pintype "bidirectional"))
    )
    (net (code "146") (name "unconnected-(U1E-PE9-PadE16)") (class "Default")
      (node (ref "U1") (pin "E16") (pinfunction "PE9_E16") (pintype "bidirectional"))
    )
    (net (code "147") (name "unconnected-(U1E-PE10-PadE17)") (class "Default")
      (node (ref "U1") (pin "E17") (pinfunction "PE10_E17") (pintype "bidirectional"))
    )
    (net (code "148") (name "unconnected-(U1F-PF2-PadT18)") (class "Default")
      (node (ref "U1") (pin "T18") (pinfunction "PF2_T18") (pintype "bidirectional"))
    )
    (net (code "149") (name "unconnected-(U1F-PF7-PadG16)") (class "Default")
      (node (ref "U1") (pin "G16") (pinfunction "PF7_G16") (pintype "bidirectional"))
    )
    (net (code "150") (name "unconnected-(U1F-PF8-PadG17)") (class "Default")
      (node (ref "U1") (pin "G17") (pinfunction "PF8_G17") (pintype "bidirectional"))
    )
    (net (code "151") (name "unconnected-(U1F-PF9-PadG18)") (class "Default")
      (node (ref "U1") (pin "G18") (pinfunction "PF9_G18") (pintype "bidirectional"))
    )
    (net (code "152") (name "unconnected-(U1F-PF10-PadH16)") (class "Default")
      (node (ref "U1") (pin "H16") (pinfunction "PF10_H16") (pintype "bidirectional"))
    )
    (net (code "153") (name "unconnected-(U1G-PG8-PadD16)") (class "Default")
      (node (ref "U1") (pin "D16") (pinfunction "PG8_D16") (pintype "bidirectional"))
    )
    (net (code "154") (name "unconnected-(U1G-PG9-PadM17)") (class "Default")
      (node (ref "U1") (pin "M17") (pinfunction "PG9_M17") (pintype "bidirectional"))
    )
    (net (code "155") (name "unconnected-(U1G-PG10-PadC18)") (class "Default")
      (node (ref "U1") (pin "C18") (pinfunction "PG10_C18") (pintype "bidirectional"))
    )
    (net (code "156") (name "unconnected-(U1H-PH2-PadB13)") (class "Default")
      (node (ref "U1") (pin "B13") (pinfunction "PH2_B13") (pintype "bidirectional"))
    )
    (net (code "157") (name "unconnected-(U1H-PH3-PadC13)") (class "Default")
      (node (ref "U1") (pin "C13") (pinfunction "PH3_C13") (pintype "bidirectional"))
    )
    (net (code "158") (name "unconnected-(U1H-PH6-PadB5)") (class "Default")
      (node (ref "U1") (pin "B5") (pinfunction "PH6_B5") (pintype "bidirectional"))
    )
    (net (code "159") (name "unconnected-(U1H-PH7-PadC5)") (class "Default")
      (node (ref "U1") (pin "C5") (pinfunction "PH7_C5") (pintype "bidirectional"))
    )
    (net (code "160") (name "unconnected-(U1I-PI10-PadB4)") (class "Default")
      (node (ref "U1") (pin "B4") (pinfunction "PI10_B4") (pintype "bidirectional"))
    )
    (net (code "161") (name "unconnected-(U1I-PI11-PadC4)") (class "Default")
      (node (ref "U1") (pin "C4") (pinfunction "PI11_C4") (pintype "bidirectional"))
    )
  )
)
